# Schematic.net
KiCad netlist of a schematic drawn in EAGLE
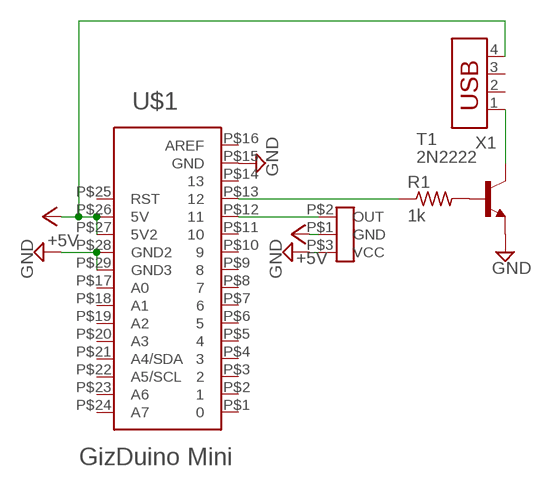
[diagram p0: schematic, sheet 1]

(export (version "E")
  (design (tool "Eeschema 10.0.6"))
  (components
    (comp (ref "R1")
      (value "1k")
      (footprint "eagle-import:0204_7")
      (libsource (lib "eagle-import") (part "R-US_0204/7"))
    )
    (comp (ref "T1")
      (value "2N2222")
      (footprint "eagle-import:TO18")
      (libsource (lib "eagle-import") (part "2N2222"))
    )
    (comp (ref "U$1")
      (value "GIZDUINO-MINI")
      (footprint "eagle-import:GIZDUINO-MINI")
      (libsource (lib "eagle-import") (part "GIZDUINO-MINI"))
    )
    (comp (ref "U1")
      (value "SOUND_SENSOR_MODULE")
      (footprint "eagle-import:SOUND_SENSOR_MODULE")
      (libsource (lib "eagle-import") (part "SOUND_SENSOR_MODULE"))
    )
    (comp (ref "X1")
      (value "USB-787616")
      (footprint "eagle-import:USB")
      (libsource (lib "eagle-import") (part "USB-787616"))
    )
  )
  (nets
    (net (code "1") (name "+5V") (class "Default")
      (node (ref "U$1") (pin "P$26") (pinfunction "5V_P$26") (pintype "bidirectional"))
      (node (ref "U$1") (pin "P$27") (pinfunction "5V2_P$27") (pintype "bidirectional"))
      (node (ref "U1") (pin "P$1") (pinfunction "GND_P$1") (pintype "bidirectional"))
      (node (ref "X1") (pin "4") (pinfunction "4_4") (pintype "passive"))
    )
    (net (code "2") (name "GND") (class "Default")
      (node (ref "T1") (pin "1") (pinfunction "E_1") (pintype "passive"))
      (node (ref "U$1") (pin "P$15") (pinfunction "GND_P$15") (pintype "bidirectional"))
      (node (ref "U$1") (pin "P$28") (pinfunction "GND2_P$28") (pintype "bidirectional"))
      (node (ref "U$1") (pin "P$29") (pinfunction "GND3_P$29") (pintype "bidirectional"))
      (node (ref "U1") (pin "P$3") (pinfunction "VCC_P$3") (pintype "bidirectional"))
    )
    (net (code "3") (name "Net-(T1-B)") (class "Default")
      (node (ref "R1") (pin "2") (pinfunction "2_2") (pintype "passive"))
      (node (ref "T1") (pin "2") (pinfunction "B_2") (pintype "passive"))
    )
    (net (code "4") (name "Net-(T1-C)") (class "Default")
      (node (ref "T1") (pin "3") (pinfunction "C_3") (pintype "passive"))
      (node (ref "X1") (pin "1") (pinfunction "1_1") (pintype "passive"))
    )
    (net (code "5") (name "Net-(U$1-11)") (class "Default")
      (node (ref "U$1") (pin "P$12") (pinfunction "11_P$12") (pintype "bidirectional"))
      (node (ref "U1") (pin "P$2") (pinfunction "OUT_P$2") (pintype "bidirectional"))
    )
    (net (code "6") (name "Net-(U$1-12)") (class "Default")
      (node (ref "R1") (pin "1") (pinfunction "1_1") (pintype "passive"))
      (node (ref "U$1") (pin "P$13") (pinfunction "12_P$13") (pintype "bidirectional"))
    )
    (net (code "7") (name "unconnected-(U$1-0-PadP$1)") (class "Default")
      (node (ref "U$1") (pin "P$1") (pinfunction "0_P$1") (pintype "bidirectional"))
    )
    (net (code "8") (name "unconnected-(U$1-1-PadP$2)") (class "Default")
      (node (ref "U$1") (pin "P$2") (pinfunction "1_P$2") (pintype "bidirectional"))
    )
    (net (code "9") (name "unconnected-(U$1-2-PadP$3)") (class "Default")
      (node (ref "U$1") (pin "P$3") (pinfunction "2_P$3") (pintype "bidirectional"))
    )
    (net (code "10") (name "unconnected-(U$1-3-PadP$4)") (class "Default")
      (node (ref "U$1") (pin "P$4") (pinfunction "3_P$4") (pintype "bidirectional"))
    )
    (net (code "11") (name "unconnected-(U$1-4-PadP$5)") (class "Default")
      (node (ref "U$1") (pin "P$5") (pinfunction "4_P$5") (pintype "bidirectional"))
    )
    (net (code "12") (name "unconnected-(U$1-5-PadP$6)") (class "Default")
      (node (ref "U$1") (pin "P$6") (pinfunction "5_P$6") (pintype "bidirectional"))
    )
    (net (code "13") (name "unconnected-(U$1-6-PadP$7)") (class "Default")
      (node (ref "U$1") (pin "P$7") (pinfunction "6_P$7") (pintype "bidirectional"))
    )
    (net (code "14") (name "unconnected-(U$1-7-PadP$8)") (class "Default")
      (node (ref "U$1") (pin "P$8") (pinfunction "7_P$8") (pintype "bidirectional"))
    )
    (net (code "15") (name "unconnected-(U$1-8-PadP$9)") (class "Default")
      (node (ref "U$1") (pin "P$9") (pinfunction "8_P$9") (pintype "bidirectional"))
    )
    (net (code "16") (name "unconnected-(U$1-9-PadP$10)") (class "Default")
      (node (ref "U$1") (pin "P$10") (pinfunction "9_P$10") (pintype "bidirectional"))
    )
    (net (code "17") (name "unconnected-(U$1-10-PadP$11)") (class "Default")
      (node (ref "U$1") (pin "P$11") (pinfunction "10_P$11") (pintype "bidirectional"))
    )
    (net (code "18") (name "unconnected-(U$1-13-PadP$14)") (class "Default")
      (node (ref "U$1") (pin "P$14") (pinfunction "13_P$14") (pintype "bidirectional"))
    )
    (net (code "19") (name "unconnected-(U$1-A0-PadP$17)") (class "Default")
      (node (ref "U$1") (pin "P$17") (pinfunction "A0_P$17") (pintype "bidirectional"))
    )
    (net (code "20") (name "unconnected-(U$1-A1-PadP$18)") (class "Default")
      (node (ref "U$1") (pin "P$18") (pinfunction "A1_P$18") (pintype "bidirectional"))
    )
    (net (code "21") (name "unconnected-(U$1-A2-PadP$19)") (class "Default")
      (node (ref "U$1") (pin "P$19") (pinfunction "A2_P$19") (pintype "bidirectional"))
    )
    (net (code "22") (name "unconnected-(U$1-A3-PadP$20)") (class "Default")
      (node (ref "U$1") (pin "P$20") (pinfunction "A3_P$20") (pintype "bidirectional"))
    )
    (net (code "23") (name "unconnected-(U$1-A4{slash}SDA-PadP$21)") (class "Default")
      (node (ref "U$1") (pin "P$21") (pinfunction "A4/SDA_P$21") (pintype "bidirectional"))
    )
    (net (code "24") (name "unconnected-(U$1-A5{slash}SCL-PadP$22)") (class "Default")
      (node (ref "U$1") (pin "P$22") (pinfunction "A5/SCL_P$22") (pintype "bidirectional"))
    )
    (net (code "25") (name "unconnected-(U$1-A6-PadP$23)") (class "Default")
      (node (ref "U$1") (pin "P$23") (pinfunction "A6_P$23") (pintype "bidirectional"))
    )
    (net (code "26") (name "unconnected-(U$1-A7-PadP$24)") (class "Default")
      (node (ref "U$1") (pin "P$24") (pinfunction "A7_P$24") (pintype "bidirectional"))
    )
    (net (code "27") (name "unconnected-(U$1-AREF-PadP$16)") (class "Default")
      (node (ref "U$1") (pin "P$16") (pinfunction "AREF_P$16") (pintype "bidirectional"))
    )
    (net (code "28") (name "unconnected-(U$1-RST-PadP$25)") (class "Default")
      (node (ref "U$1") (pin "P$25") (pinfunction "RST_P$25") (pintype "bidirectional"))
    )
    (net (code "29") (name "unconnected-(X1-Pad2)") (class "Default")
      (node (ref "X1") (pin "2") (pinfunction "2_2") (pintype "passive"))
    )
    (net (code "30") (name "unconnected-(X1-Pad3)") (class "Default")
      (node (ref "X1") (pin "3") (pinfunction "3_3") (pintype "passive"))
    )
  )
)
